# Component_Schematics.net
KiCad netlist of a schematic drawn in Altium Designer
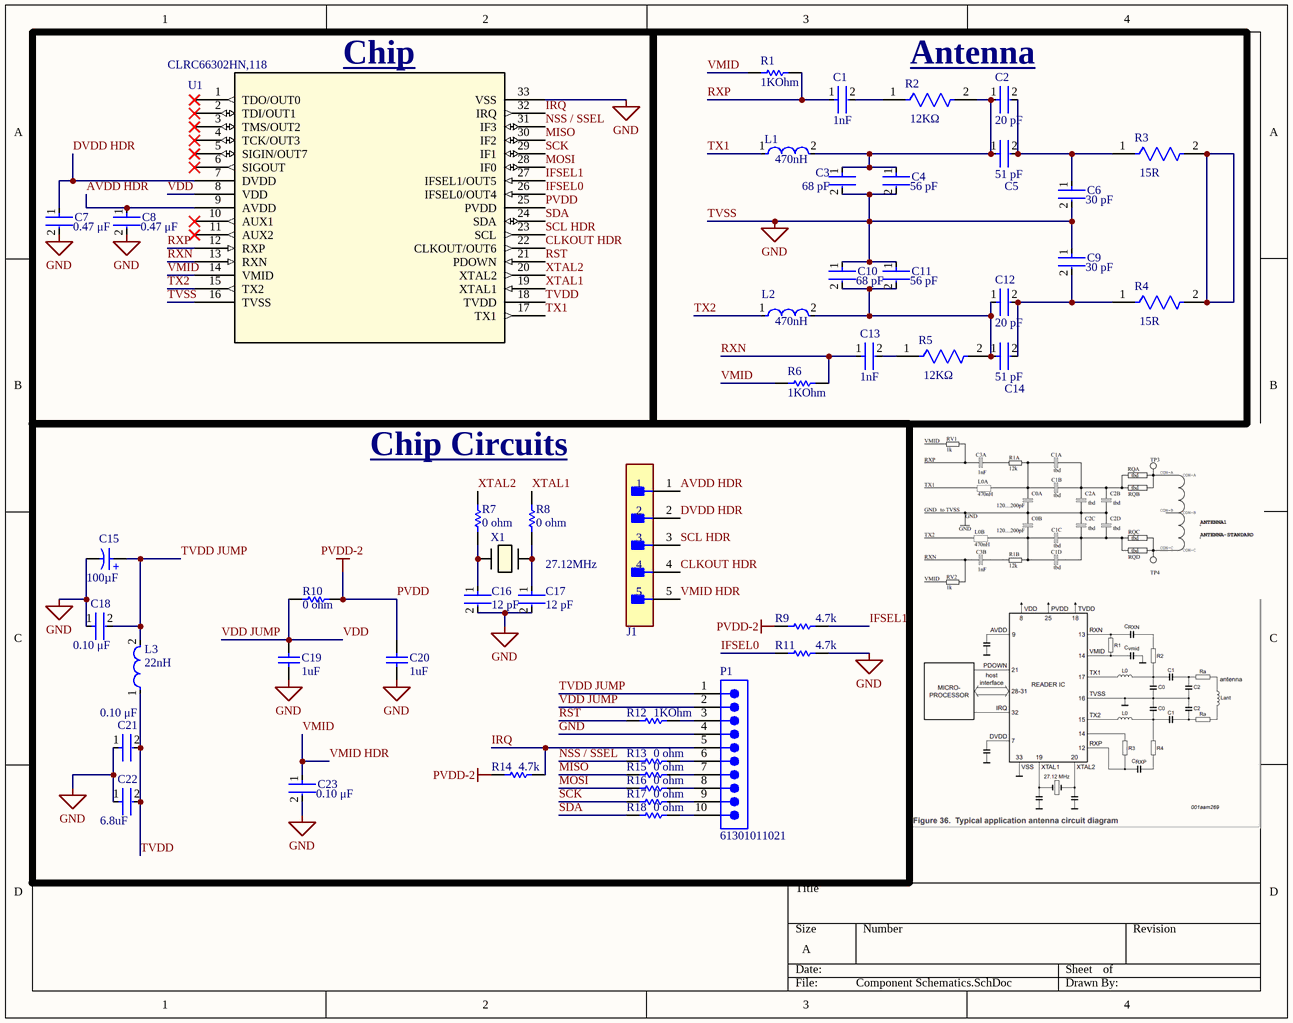
[diagram p0: Component Schematics.SchDoc]

(export (version "E")
  (design (tool "Eeschema 10.0.6"))
  (components
    (comp (ref "C1")
      (value "06035C102KAT2A")
      (footprint "FP-0603-L_1_6_0_15-W_0_81-IPC_A")
      (description "General Purpose Ceramic Capacitor, 0603, 1nF, 10%, X7R, 15%, 50V")
      (fields
        (field (name "CAPACITANCE") "1nF")
        (field (name "VOLTAGE") "50V")
        (field (name "TOLERANCE") "10%")
      )
      (libsource (lib "Altium Content Vault") (part "02cd4be3c70576c341d710602a673aa"))
    )
    (comp (ref "C2")
      (value "C0402C200J5GACTU")
      (footprint "FP-C0402-BB-MFG")
      (description "CAP CER 20PF 50V 5% NP0 0402")
      (fields
        (field (name "OCTOPART") "https://octopart.com/c0402c200j5gactu-kemet-9143900")
        (field (name "TOLERANCE") "0.05")
        (field (name "CAPACITANCE") "20 pF")
      )
      (libsource (lib "Altium Content Vault") (part "b4654b650e69147ec39a6b967a45e02"))
    )
    (comp (ref "C3")
      (value "C0402C680J5GACTU")
      (footprint "FP-C0402-BB-MFG")
      (description "CAP CER 68PF 50V 5% NP0 0402")
      (fields
        (field (name "MANUFACTURER") "Kemet")
        (field (name "CAPACITANCE") "68 pF")
        (field (name "TOLERANCE") "0.05")
      )
      (libsource (lib "Altium Content Vault") (part "b4654b650e69147ec39a6b967a45e02"))
    )
    (comp (ref "C4")
      (value "C0603C560J5GACTU")
      (footprint "FP-C0603C-CF-MFG")
      (description "CAP CER 56PF 50V C0G/NP0 0603")
      (fields
        (field (name "OCTOPART") "https://octopart.com/c0603c560j5gactu-kemet-107933")
        (field (name "CAPACITANCE") "56 pF")
        (field (name "MANUFACTURER") "KEMET")
      )
      (libsource (lib "Altium Content Vault") (part "b4654b650e69147ec39a6b967a45e02"))
    )
    (comp (ref "C5")
      (value "C0603C510J5GACTU")
      (footprint "FP-C0603C-CF-MFG")
      (description "CAP CER 51PF 50V 5% NP0 0603")
      (fields
        (field (name "TOLERANCE") "0.05")
        (field (name "OCTOPART") "https://octopart.com/c0603c510j5gactu-kemet-9143750")
        (field (name "CAPACITANCE") "51 pF")
      )
      (libsource (lib "Altium Content Vault") (part "b4654b650e69147ec39a6b967a45e02"))
    )
    (comp (ref "C6")
      (value "30 pF")
      (footprint "FP-C0603C-CF-MFG")
      (description "CAP CER 30PF 50V 5% NP0 0603")
      (fields
        (field (name "MANUFACTURER PART NUMBER") "C0603C300J5GACTU")
        (field (name "MANUFACTURER") "KEMET")
      )
      (libsource (lib "Altium Content Vault") (part "b4654b650e69147ec39a6b967a45e02"))
    )
    (comp (ref "C7")
      (value "C0805C474K5RACTU")
      (footprint "FP-C0805C-DN-MFG")
      (description "CAP CER 0.47UF 50V 10% X7R 0805")
      (fields
        (field (name "CAPACITANCE") "0.47 μF")
        (field (name "MANUFACTURER") "KEMET")
        (field (name "OCTOPART") "https://octopart.com/c0805c474k5ractu-kemet-144543")
      )
      (libsource (lib "Altium Content Vault") (part "b4654b650e69147ec39a6b967a45e02"))
    )
    (comp (ref "C8")
      (value "C0805C474K5RACTU")
      (footprint "FP-C0805C-DN-MFG")
      (description "CAP CER 0.47UF 50V 10% X7R 0805")
      (fields
        (field (name "CAPACITANCE") "0.47 μF")
        (field (name "MANUFACTURER") "KEMET")
        (field (name "OCTOPART") "https://octopart.com/c0805c474k5ractu-kemet-144543")
      )
      (libsource (lib "Altium Content Vault") (part "b4654b650e69147ec39a6b967a45e02"))
    )
    (comp (ref "C9")
      (value "30 pF")
      (footprint "FP-C0603C-CF-MFG")
      (description "CAP CER 30PF 50V 5% NP0 0603")
      (fields
        (field (name "MANUFACTURER PART NUMBER") "C0603C300J5GACTU")
        (field (name "MANUFACTURER") "KEMET")
      )
      (libsource (lib "Altium Content Vault") (part "b4654b650e69147ec39a6b967a45e02"))
    )
    (comp (ref "C10")
      (value "C0402C680J5GACTU")
      (footprint "FP-C0402-BB-MFG")
      (description "CAP CER 68PF 50V 5% NP0 0402")
      (fields
        (field (name "MANUFACTURER") "Kemet")
        (field (name "CAPACITANCE") "68 pF")
        (field (name "TOLERANCE") "0.05")
      )
      (libsource (lib "Altium Content Vault") (part "b4654b650e69147ec39a6b967a45e02"))
    )
    (comp (ref "C11")
      (value "C0603C560J5GACTU")
      (footprint "FP-C0603C-CF-MFG")
      (description "CAP CER 56PF 50V C0G/NP0 0603")
      (fields
        (field (name "OCTOPART") "https://octopart.com/c0603c560j5gactu-kemet-107933")
        (field (name "CAPACITANCE") "56 pF")
        (field (name "MANUFACTURER") "KEMET")
      )
      (libsource (lib "Altium Content Vault") (part "b4654b650e69147ec39a6b967a45e02"))
    )
    (comp (ref "C12")
      (value "C0402C200J5GACTU")
      (footprint "FP-C0402-BB-MFG")
      (description "CAP CER 20PF 50V 5% NP0 0402")
      (fields
        (field (name "OCTOPART") "https://octopart.com/c0402c200j5gactu-kemet-9143900")
        (field (name "TOLERANCE") "0.05")
        (field (name "CAPACITANCE") "20 pF")
      )
      (libsource (lib "Altium Content Vault") (part "b4654b650e69147ec39a6b967a45e02"))
    )
    (comp (ref "C13")
      (value "06035C102KAT2A")
      (footprint "FP-0603-L_1_6_0_15-W_0_81-IPC_A")
      (description "General Purpose Ceramic Capacitor, 0603, 1nF, 10%, X7R, 15%, 50V")
      (fields
        (field (name "CAPACITANCE") "1nF")
        (field (name "VOLTAGE") "50V")
        (field (name "TOLERANCE") "10%")
      )
      (libsource (lib "Altium Content Vault") (part "02cd4be3c70576c341d710602a673aa"))
    )
    (comp (ref "C14")
      (value "C0603C510J5GACTU")
      (footprint "FP-C0603C-CF-MFG")
      (description "CAP CER 51PF 50V 5% NP0 0603")
      (fields
        (field (name "TOLERANCE") "0.05")
        (field (name "OCTOPART") "https://octopart.com/c0603c510j5gactu-kemet-9143750")
        (field (name "CAPACITANCE") "51 pF")
      )
      (libsource (lib "Altium Content Vault") (part "b4654b650e69147ec39a6b967a45e02"))
    )
    (comp (ref "C15")
      (value "865060653010")
      (footprint "WCAP-ASLL_D8H10.5")
      (fields (field (name "CAPACITANCE") "100µF") (field (name "TOLERANCE") "20%"))
      (libsource (lib "Altium Content Vault") (part "Capacitor_Polarized"))
    )
    (comp (ref "C16")
      (value "12 pF")
      (footprint "FP-C0603C-CF-MFG")
      (description "Ceramic Capacitor 12Pf 50V, C0G, 5%, 0603, Full Reel")
      (fields (field (name "MANUFACTURER") "KEMET") (field (name "TOLERANCE") "0.05"))
      (libsource (lib "Altium Content Vault") (part "b4654b650e69147ec39a6b967a45e02"))
    )
    (comp (ref "C17")
      (value "12 pF")
      (footprint "FP-C0603C-CF-MFG")
      (description "Ceramic Capacitor 12Pf 50V, C0G, 5%, 0603, Full Reel")
      (fields (field (name "MANUFACTURER") "KEMET") (field (name "TOLERANCE") "0.05"))
      (libsource (lib "Altium Content Vault") (part "b4654b650e69147ec39a6b967a45e02"))
    )
    (comp (ref "C18")
      (value "C0402C104K8PACTU")
      (footprint "FP-C0402-BB-MFG")
      (description "CAP CER 0.1UF 10V X5R 0402")
      (fields
        (field (name "CAPACITANCE") "0.10 μF")
        (field (name "MANUFACTURER") "Kemet")
        (field (name "TOLERANCE") "0.1")
      )
      (libsource (lib "Altium Content Vault") (part "b4654b650e69147ec39a6b967a45e02"))
    )
    (comp (ref "C19")
      (value "C1206C105K5RACTU")
      (footprint "CAPC3216X110X50LL20T25")
      (description "Chip Capacitor, 1 uF, +/- 10%, 50 V, -55 to 125 degC, 1206 (3216 Metric), RoHS, Tape and Reel")
      (fields
        (field (name "CAPACITANCE") "1uF")
        (field (name "MANUFACTURER") "Kemet")
        (field (name "TOLERANCE") "10%")
      )
      (libsource (lib "Altium Content Vault") (part "CAP-NP-2"))
    )
    (comp (ref "C20")
      (value "C1206C105K5RACTU")
      (footprint "CAPC3216X110X50LL20T25")
      (description "Chip Capacitor, 1 uF, +/- 10%, 50 V, -55 to 125 degC, 1206 (3216 Metric), RoHS, Tape and Reel")
      (fields
        (field (name "CAPACITANCE") "1uF")
        (field (name "MANUFACTURER") "Kemet")
        (field (name "TOLERANCE") "10%")
      )
      (libsource (lib "Altium Content Vault") (part "CAP-NP-2"))
    )
    (comp (ref "C21")
      (value "C0402C104K8PACTU")
      (footprint "FP-C0402-BB-MFG")
      (description "CAP CER 0.1UF 10V X5R 0402")
      (fields
        (field (name "CAPACITANCE") "0.10 μF")
        (field (name "MANUFACTURER") "Kemet")
        (field (name "TOLERANCE") "0.1")
      )
      (libsource (lib "Altium Content Vault") (part "b4654b650e69147ec39a6b967a45e02"))
    )
    (comp (ref "C22")
      (value "C4532X7R1H685K250KB")
      (footprint "FP-C4532-250-0_4-IPC_C")
      (description "Multilayer Ceramic Capacitors 6.8uF ±10% 50V X7R SMD 1812")
      (fields
        (field (name "VOLTAGE") "50V")
        (field (name "CAPACITANCE") "6.8uF")
        (field (name "TOLERANCE") "10%")
      )
      (libsource (lib "Altium Content Vault") (part "02cd4be3c70576c341d710602a673aa"))
    )
    (comp (ref "C23")
      (value "C0402C104K8PACTU")
      (footprint "FP-C0402-BB-MFG")
      (description "CAP CER 0.1UF 10V X5R 0402")
      (fields
        (field (name "CAPACITANCE") "0.10 μF")
        (field (name "MANUFACTURER") "Kemet")
        (field (name "TOLERANCE") "0.1")
      )
      (libsource (lib "Altium Content Vault") (part "b4654b650e69147ec39a6b967a45e02"))
    )
    (comp (ref "J1")
      (value "22-28-4050")
      (footprint "FP-22-28-4050-MFG")
      (libsource (lib "Altium Content Vault") (part "bf93c07fd2649a848d0ec8585582aab"))
    )
    (comp (ref "L1")
      (value "IHLP2020CZERR47M01")
      (footprint "FP-IHLP-2020CZ-FP_1_905x2-MFG")
      (description "Fixed Inductors Commercial High Saturation Series 0.47uH 12.2A 7.04mΩ 20%")
      (fields (field (name "TOLERANCE") "20%") (field (name "INDUCTANCE") "470nH"))
      (libsource (lib "Altium Content Vault") (part "725321dda6339637d4d059423bc1c3c"))
    )
    (comp (ref "L2")
      (value "IHLP2020CZERR47M01")
      (footprint "FP-IHLP-2020CZ-FP_1_905x2-MFG")
      (description "Fixed Inductors Commercial High Saturation Series 0.47uH 12.2A 7.04mΩ 20%")
      (fields (field (name "TOLERANCE") "20%") (field (name "INDUCTANCE") "470nH"))
      (libsource (lib "Altium Content Vault") (part "725321dda6339637d4d059423bc1c3c"))
    )
    (comp (ref "L3")
      (value "LQW18AN22NG00D")
      (footprint "FP-LQW18AN_00-MFG")
      (description "Wire Wound RF Inductor 22nH ±2% 500mA 0.17Ω 0603 (1608)")
      (fields (field (name "TOLERANCE") "2%") (field (name "INDUCTANCE") "22nH"))
      (libsource (lib "Altium Content Vault") (part "725321dda6339637d4d059423bc1c3c"))
    )
    (comp (ref "P1")
      (value "61301011021")
      (footprint "61301011021")
      (libsource (lib "Altium Content Vault") (part "Header_Male_1R_10P"))
    )
    (comp (ref "R1")
      (value "RC0805FR-071KL")
      (footprint "RESC2013X60X35ML10T20")
      (description "Chip Resistor, 1 KOhm, +/- 1%, 125 mW, -55 to 155 degC, 0805 (2012 Metric), RoHS, Tape and Reel")
      (fields
        (field (name "RESISTANCE") "1KOhm")
        (field (name "TOLERANCE") "1%")
        (field (name "MANUFACTURER") "Yageo")
      )
      (libsource (lib "Altium Content Vault") (part "RES-2"))
    )
    (comp (ref "R2")
      (value "RT1206BRD0712KL")
      (footprint "FP-RT1206-MFG")
      (description "RES SMD 12K OHM 0.1% 1/4W 1206")
      (fields
        (field (name "MANUFACTURER") "Yageo")
        (field (name "OCTOPART") "https://octopart.com/rt1206brd0712kl-yageo-1232840")
        (field (name "RESISTANCE") "12KΩ")
      )
      (libsource (lib "Altium Content Vault") (part "1029c3af85768c4190bb7ad29bc67b5"))
    )
    (comp (ref "R3")
      (value "CRCW060315R0FKEA")
      (footprint "FP-CRCW0603-e3-MFG")
      (description "RES Thick Film, 15Ω, 1%, 0.1W, 100ppm/°C, 0603")
      (fields (field (name "TOLERANCE") "1%") (field (name "RESISTANCE") "15R"))
      (libsource (lib "Altium Content Vault") (part "1029c3af85768c4190bb7ad29bc67b5"))
    )
    (comp (ref "R4")
      (value "CRCW060315R0FKEA")
      (footprint "FP-CRCW0603-e3-MFG")
      (description "RES Thick Film, 15Ω, 1%, 0.1W, 100ppm/°C, 0603")
      (fields (field (name "TOLERANCE") "1%") (field (name "RESISTANCE") "15R"))
      (libsource (lib "Altium Content Vault") (part "1029c3af85768c4190bb7ad29bc67b5"))
    )
    (comp (ref "R5")
      (value "RT1206BRD0712KL")
      (footprint "FP-RT1206-MFG")
      (description "RES SMD 12K OHM 0.1% 1/4W 1206")
      (fields
        (field (name "MANUFACTURER") "Yageo")
        (field (name "OCTOPART") "https://octopart.com/rt1206brd0712kl-yageo-1232840")
        (field (name "RESISTANCE") "12KΩ")
      )
      (libsource (lib "Altium Content Vault") (part "1029c3af85768c4190bb7ad29bc67b5"))
    )
    (comp (ref "R6")
      (value "RC0805FR-071KL")
      (footprint "RESC2013X60X35ML10T20")
      (description "Chip Resistor, 1 KOhm, +/- 1%, 125 mW, -55 to 155 degC, 0805 (2012 Metric), RoHS, Tape and Reel")
      (fields
        (field (name "RESISTANCE") "1KOhm")
        (field (name "TOLERANCE") "1%")
        (field (name "MANUFACTURER") "Yageo")
      )
      (libsource (lib "Altium Content Vault") (part "RES-2"))
    )
    (comp (ref "R7")
      (value "RC0603JR-070RL")
      (footprint "RESC1608X55X25ML10T15")
      (description "Chip Resistor, 0 Ohm, +/- 5%, 0.1 W, -55 to 155 degC, 0603 (1608 Metric), RoHS, Tape and Reel")
      (fields
        (field (name "TOLERANCE") "5%")
        (field (name "RESISTANCE") "0 ohm")
        (field (name "MANUFACTURER") "Yageo")
      )
      (libsource (lib "Altium Content Vault") (part "RES-2"))
    )
    (comp (ref "R8")
      (value "RC0603JR-070RL")
      (footprint "RESC1608X55X25ML10T15")
      (description "Chip Resistor, 0 Ohm, +/- 5%, 0.1 W, -55 to 155 degC, 0603 (1608 Metric), RoHS, Tape and Reel")
      (fields
        (field (name "TOLERANCE") "5%")
        (field (name "RESISTANCE") "0 ohm")
        (field (name "MANUFACTURER") "Yageo")
      )
      (libsource (lib "Altium Content Vault") (part "RES-2"))
    )
    (comp (ref "R9")
      (value "RK73B1JTTD472J")
      (footprint "RESC1608X55X30ML20T10")
      (fields (field (name "MANUFACTURER") "KOA Speer") (field (name "RESISTANCE") "4.7k"))
      (libsource (lib "Altium Content Vault") (part "RES"))
    )
    (comp (ref "R10")
      (value "RC0603JR-070RL")
      (footprint "RESC1608X55X25ML10T15")
      (description "Chip Resistor, 0 Ohm, +/- 5%, 0.1 W, -55 to 155 degC, 0603 (1608 Metric), RoHS, Tape and Reel")
      (fields
        (field (name "TOLERANCE") "5%")
        (field (name "RESISTANCE") "0 ohm")
        (field (name "MANUFACTURER") "Yageo")
      )
      (libsource (lib "Altium Content Vault") (part "RES-2"))
    )
    (comp (ref "R11")
      (value "RK73B1JTTD472J")
      (footprint "RESC1608X55X30ML20T10")
      (fields (field (name "MANUFACTURER") "KOA Speer") (field (name "RESISTANCE") "4.7k"))
      (libsource (lib "Altium Content Vault") (part "RES"))
    )
    (comp (ref "R12")
      (value "RC1206FR-071KL")
      (footprint "RESC3116X65X40ML10T20")
      (description "Chip Resistor, 1 KOhm, +/- 1%, 0.25 W, -55 to 155 degC, 1206 (3216 Metric), RoHS, Tape and Reel")
      (fields
        (field (name "TOLERANCE") "1%")
        (field (name "MANUFACTURER") "Yageo")
        (field (name "RESISTANCE") "1KOhm")
      )
      (libsource (lib "Altium Content Vault") (part "RES-2"))
    )
    (comp (ref "R13")
      (value "RC0603JR-070RL")
      (footprint "RESC1608X55X25ML10T15")
      (description "Chip Resistor, 0 Ohm, +/- 5%, 0.1 W, -55 to 155 degC, 0603 (1608 Metric), RoHS, Tape and Reel")
      (fields
        (field (name "TOLERANCE") "5%")
        (field (name "RESISTANCE") "0 ohm")
        (field (name "MANUFACTURER") "Yageo")
      )
      (libsource (lib "Altium Content Vault") (part "RES-2"))
    )
    (comp (ref "R14")
      (value "RK73B1JTTD472J")
      (footprint "RESC1608X55X30ML20T10")
      (fields (field (name "MANUFACTURER") "KOA Speer") (field (name "RESISTANCE") "4.7k"))
      (libsource (lib "Altium Content Vault") (part "RES"))
    )
    (comp (ref "R15")
      (value "RC0603JR-070RL")
      (footprint "RESC1608X55X25ML10T15")
      (description "Chip Resistor, 0 Ohm, +/- 5%, 0.1 W, -55 to 155 degC, 0603 (1608 Metric), RoHS, Tape and Reel")
      (fields
        (field (name "TOLERANCE") "5%")
        (field (name "RESISTANCE") "0 ohm")
        (field (name "MANUFACTURER") "Yageo")
      )
      (libsource (lib "Altium Content Vault") (part "RES-2"))
    )
    (comp (ref "R16")
      (value "RC0603JR-070RL")
      (footprint "RESC1608X55X25ML10T15")
      (description "Chip Resistor, 0 Ohm, +/- 5%, 0.1 W, -55 to 155 degC, 0603 (1608 Metric), RoHS, Tape and Reel")
      (fields
        (field (name "TOLERANCE") "5%")
        (field (name "RESISTANCE") "0 ohm")
        (field (name "MANUFACTURER") "Yageo")
      )
      (libsource (lib "Altium Content Vault") (part "RES-2"))
    )
    (comp (ref "R17")
      (value "RC0603JR-070RL")
      (footprint "RESC1608X55X25ML10T15")
      (description "Chip Resistor, 0 Ohm, +/- 5%, 0.1 W, -55 to 155 degC, 0603 (1608 Metric), RoHS, Tape and Reel")
      (fields
        (field (name "TOLERANCE") "5%")
        (field (name "RESISTANCE") "0 ohm")
        (field (name "MANUFACTURER") "Yageo")
      )
      (libsource (lib "Altium Content Vault") (part "RES-2"))
    )
    (comp (ref "R18")
      (value "RC0603JR-070RL")
      (footprint "RESC1608X55X25ML10T15")
      (description "Chip Resistor, 0 Ohm, +/- 5%, 0.1 W, -55 to 155 degC, 0603 (1608 Metric), RoHS, Tape and Reel")
      (fields
        (field (name "TOLERANCE") "5%")
        (field (name "RESISTANCE") "0 ohm")
        (field (name "MANUFACTURER") "Yageo")
      )
      (libsource (lib "Altium Content Vault") (part "RES-2"))
    )
    (comp (ref "U1")
      (value "CLRC66302HN,118")
      (footprint "HVQFN32_SOT617-1_NXP")
      (description "Telecom Circuit, 1-Func, CMOS, PQCC32")
      (fields
        (field (name "MANUFACTURER") "NXP Semiconductors")
        (field (name "COPYRIGHT") "Copyright (C) 2023 Ultra Librarian. All rights reserved.")
      )
      (libsource (lib "*") (part "CLRC66302HN,118"))
    )
    (comp (ref "X1")
      (value "LFXTAL036075BULK")
      (footprint "XTAL_LFXTAL0360_IQD")
      (description "Parallel - Fundamental Quartz Crystal, 27.12MHz Nom")
      (fields
        (field (name "MANUFACTURER") "IQD")
        (field (name "CLOCK SPEED") "27.12MHz")
        (field (name "COPYRIGHT") "Copyright (C) 2023 Ultra Librarian. All rights reserved.")
      )
      (libsource (lib "LFXTAL036075BULK") (part "LFXTAL036075BULK"))
    )
  )
  (nets
    (net (code "1") (name "/AVDD HDR") (class "Default")
      (node (ref "C8") (pin "1") (pinfunction "1_1") (pintype "passive"))
      (node (ref "J1") (pin "1") (pinfunction "1_1") (pintype "passive"))
      (node (ref "U1") (pin "9") (pinfunction "AVDD_9") (pintype "power_in"))
    )
    (net (code "2") (name "/CLKOUT HDR") (class "Default")
      (node (ref "J1") (pin "4") (pinfunction "4_4") (pintype "passive"))
      (node (ref "U1") (pin "22") (pinfunction "CLKOUT/OUT6_22") (pintype "output"))
    )
    (net (code "3") (name "/DVDD HDR") (class "Default")
      (node (ref "C7") (pin "1") (pinfunction "1_1") (pintype "passive"))
      (node (ref "J1") (pin "2") (pinfunction "2_2") (pintype "passive"))
      (node (ref "U1") (pin "7") (pinfunction "DVDD_7") (pintype "power_in"))
    )
    (net (code "4") (name "/IFSEL0") (class "Default")
      (node (ref "R11") (pin "2") (pinfunction "2_2") (pintype "passive"))
      (node (ref "U1") (pin "26") (pinfunction "IFSEL0/OUT4_26") (pintype "input"))
    )
    (net (code "5") (name "/IFSEL1") (class "Default")
      (node (ref "R9") (pin "1") (pinfunction "1_1") (pintype "passive"))
      (node (ref "U1") (pin "27") (pinfunction "IFSEL1/OUT5_27") (pintype "input"))
    )
    (net (code "6") (name "/IRQ") (class "Default")
      (node (ref "P1") (pin "5") (pinfunction "5_5") (pintype "passive"))
      (node (ref "R14") (pin "2") (pinfunction "2_2") (pintype "passive"))
      (node (ref "U1") (pin "32") (pinfunction "IRQ_32") (pintype "output"))
    )
    (net (code "7") (name "/MISO") (class "Default")
      (node (ref "R15") (pin "1") (pinfunction "1_1") (pintype "passive"))
      (node (ref "U1") (pin "30") (pinfunction "IF2_30") (pintype "bidirectional"))
    )
    (net (code "8") (name "/MOSI") (class "Default")
      (node (ref "R16") (pin "1") (pinfunction "1_1") (pintype "passive"))
      (node (ref "U1") (pin "28") (pinfunction "IF0_28") (pintype "bidirectional"))
    )
    (net (code "9") (name "/NSS {slash} SSEL") (class "Default")
      (node (ref "R13") (pin "1") (pinfunction "1_1") (pintype "passive"))
      (node (ref "U1") (pin "31") (pinfunction "IF3_31") (pintype "bidirectional"))
    )
    (net (code "10") (name "/RST") (class "Default")
      (node (ref "R12") (pin "1") (pinfunction "1_1") (pintype "passive"))
      (node (ref "U1") (pin "21") (pinfunction "PDOWN_21") (pintype "input"))
    )
    (net (code "11") (name "/RXN") (class "Default")
      (node (ref "C13") (pin "1") (pinfunction "1_1") (pintype "passive"))
      (node (ref "R6") (pin "1") (pinfunction "1_1") (pintype "passive"))
      (node (ref "U1") (pin "13") (pinfunction "RXN_13") (pintype "input"))
    )
    (net (code "12") (name "/RXP") (class "Default")
      (node (ref "C1") (pin "1") (pinfunction "1_1") (pintype "passive"))
      (node (ref "R1") (pin "1") (pinfunction "1_1") (pintype "passive"))
      (node (ref "U1") (pin "12") (pinfunction "RXP_12") (pintype "input"))
    )
    (net (code "13") (name "/SCK") (class "Default")
      (node (ref "R17") (pin "1") (pinfunction "1_1") (pintype "passive"))
      (node (ref "U1") (pin "29") (pinfunction "IF1_29") (pintype "bidirectional"))
    )
    (net (code "14") (name "/SCL HDR") (class "Default")
      (node (ref "J1") (pin "3") (pinfunction "3_3") (pintype "passive"))
      (node (ref "U1") (pin "23") (pinfunction "SCL_23") (pintype "output"))
    )
    (net (code "15") (name "/SDA") (class "Default")
      (node (ref "R18") (pin "1") (pinfunction "1_1") (pintype "passive"))
      (node (ref "U1") (pin "24") (pinfunction "SDA_24") (pintype "bidirectional"))
    )
    (net (code "16") (name "/TVDD") (class "Default")
      (node (ref "C21") (pin "2") (pinfunction "2_2") (pintype "passive"))
      (node (ref "C22") (pin "2") (pinfunction "2_2") (pintype "passive"))
      (node (ref "L3") (pin "1") (pinfunction "1_1") (pintype "passive"))
      (node (ref "U1") (pin "18") (pinfunction "TVDD_18") (pintype "power_in"))
    )
    (net (code "17") (name "/TVDD JUMP") (class "Default")
      (node (ref "C15") (pin "1") (pinfunction "P_1") (pintype "passive"))
      (node (ref "C18") (pin "2") (pinfunction "2_2") (pintype "passive"))
      (node (ref "L3") (pin "2") (pinfunction "2_2") (pintype "passive"))
      (node (ref "P1") (pin "1") (pinfunction "1_1") (pintype "passive"))
    )
    (net (code "18") (name "/TX1") (class "Default")
      (node (ref "L1") (pin "1") (pinfunction "1_1") (pintype "passive"))
      (node (ref "U1") (pin "17") (pinfunction "TX1_17") (pintype "output"))
    )
    (net (code "19") (name "/TX2") (class "Default")
      (node (ref "L2") (pin "1") (pinfunction "1_1") (pintype "passive"))
      (node (ref "U1") (pin "15") (pinfunction "TX2_15") (pintype "output"))
    )
    (net (code "20") (name "/VDD") (class "Default")
      (node (ref "C19") (pin "2") (pinfunction "2_2") (pintype "passive"))
      (node (ref "P1") (pin "2") (pinfunction "2_2") (pintype "passive"))
      (node (ref "R10") (pin "1") (pinfunction "1_1") (pintype "passive"))
      (node (ref "U1") (pin "8") (pinfunction "VDD_8") (pintype "power_in"))
    )
    (net (code "21") (name "/VMID") (class "Default")
      (node (ref "C23") (pin "1") (pinfunction "1_1") (pintype "passive"))
      (node (ref "J1") (pin "5") (pinfunction "5_5") (pintype "passive"))
      (node (ref "R1") (pin "2") (pinfunction "2_2") (pintype "passive"))
      (node (ref "R6") (pin "2") (pinfunction "2_2") (pintype "passive"))
      (node (ref "U1") (pin "14") (pinfunction "VMID_14") (pintype "power_in"))
    )
    (net (code "22") (name "/XTAL1") (class "Default")
      (node (ref "R8") (pin "1") (pinfunction "1_1") (pintype "passive"))
      (node (ref "U1") (pin "19") (pinfunction "XTAL1_19") (pintype "input"))
    )
    (net (code "23") (name "/XTAL2") (class "Default")
      (node (ref "R7") (pin "1") (pinfunction "1_1") (pintype "passive"))
      (node (ref "U1") (pin "20") (pinfunction "XTAL2_20") (pintype "output"))
    )
    (net (code "24") (name "GND") (class "Default")
      (node (ref "C10") (pin "1") (pinfunction "1_1") (pintype "passive"))
      (node (ref "C11") (pin "1") (pinfunction "1_1") (pintype "passive"))
      (node (ref "C15") (pin "2") (pinfunction "N_2") (pintype "passive"))
      (node (ref "C16") (pin "2") (pinfunction "2_2") (pintype "passive"))
      (node (ref "C17") (pin "2") (pinfunction "2_2") (pintype "passive"))
      (node (ref "C18") (pin "1") (pinfunction "1_1") (pintype "passive"))
      (node (ref "C19") (pin "1") (pinfunction "1_1") (pintype "passive"))
      (node (ref "C20") (pin "1") (pinfunction "1_1") (pintype "passive"))
      (node (ref "C21") (pin "1") (pinfunction "1_1") (pintype "passive"))
      (node (ref "C22") (pin "1") (pinfunction "1_1") (pintype "passive"))
      (node (ref "C23") (pin "2") (pinfunction "2_2") (pintype "passive"))
      (node (ref "C3") (pin "2") (pinfunction "2_2") (pintype "passive"))
      (node (ref "C4") (pin "2") (pinfunction "2_2") (pintype "passive"))
      (node (ref "C6") (pin "2") (pinfunction "2_2") (pintype "passive"))
      (node (ref "C7") (pin "2") (pinfunction "2_2") (pintype "passive"))
      (node (ref "C8") (pin "2") (pinfunction "2_2") (pintype "passive"))
      (node (ref "C9") (pin "1") (pinfunction "1_1") (pintype "passive"))
      (node (ref "P1") (pin "4") (pinfunction "4_4") (pintype "passive"))
      (node (ref "R11") (pin "1") (pinfunction "1_1") (pintype "passive"))
      (node (ref "U1") (pin "16") (pinfunction "TVSS_16") (pintype "power_in"))
      (node (ref "U1") (pin "33") (pinfunction "VSS_33") (pintype "power_in"))
    )
    (net (code "25") (name "Net-(C1-Pad2)") (class "Default")
      (node (ref "C1") (pin "2") (pinfunction "2_2") (pintype "passive"))
      (node (ref "R2") (pin "1") (pinfunction "1_1") (pintype "passive"))
    )
    (net (code "26") (name "Net-(C2-Pad1)") (class "Default")
      (node (ref "C2") (pin "1") (pinfunction "1_1") (pintype "passive"))
      (node (ref "C3") (pin "1") (pinfunction "1_1") (pintype "passive"))
      (node (ref "C4") (pin "1") (pinfunction "1_1") (pintype "passive"))
      (node (ref "C5") (pin "1") (pinfunction "1_1") (pintype "passive"))
      (node (ref "L1") (pin "2") (pinfunction "2_2") (pintype "passive"))
      (node (ref "R2") (pin "2") (pinfunction "2_2") (pintype "passive"))
    )
    (net (code "27") (name "Net-(C2-Pad2)") (class "Default")
      (node (ref "C2") (pin "2") (pinfunction "2_2") (pintype "passive"))
      (node (ref "C5") (pin "2") (pinfunction "2_2") (pintype "passive"))
      (node (ref "C6") (pin "1") (pinfunction "1_1") (pintype "passive"))
      (node (ref "R3") (pin "1") (pinfunction "1_1") (pintype "passive"))
    )
    (net (code "28") (name "Net-(C10-Pad2)") (class "Default")
      (node (ref "C10") (pin "2") (pinfunction "2_2") (pintype "passive"))
      (node (ref "C11") (pin "2") (pinfunction "2_2") (pintype "passive"))
      (node (ref "C12") (pin "1") (pinfunction "1_1") (pintype "passive"))
      (node (ref "C14") (pin "1") (pinfunction "1_1") (pintype "passive"))
      (node (ref "L2") (pin "2") (pinfunction "2_2") (pintype "passive"))
      (node (ref "R5") (pin "2") (pinfunction "2_2") (pintype "passive"))
    )
    (net (code "29") (name "Net-(C12-Pad2)") (class "Default")
      (node (ref "C12") (pin "2") (pinfunction "2_2") (pintype "passive"))
      (node (ref "C14") (pin "2") (pinfunction "2_2") (pintype "passive"))
      (node (ref "C9") (pin "2") (pinfunction "2_2") (pintype "passive"))
      (node (ref "R4") (pin "1") (pinfunction "1_1") (pintype "passive"))
    )
    (net (code "30") (name "Net-(C13-Pad2)") (class "Default")
      (node (ref "C13") (pin "2") (pinfunction "2_2") (pintype "passive"))
      (node (ref "R5") (pin "1") (pinfunction "1_1") (pintype "passive"))
    )
    (net (code "31") (name "Net-(C16-Pad1)") (class "Default")
      (node (ref "C16") (pin "1") (pinfunction "1_1") (pintype "passive"))
      (node (ref "R7") (pin "2") (pinfunction "2_2") (pintype "passive"))
      (node (ref "X1") (pin "1") (pinfunction "1_1") (pintype "passive"))
    )
    (net (code "32") (name "Net-(C17-Pad1)") (class "Default")
      (node (ref "C17") (pin "1") (pinfunction "1_1") (pintype "passive"))
      (node (ref "R8") (pin "2") (pinfunction "2_2") (pintype "passive"))
      (node (ref "X1") (pin "2") (pinfunction "2_2") (pintype "passive"))
    )
    (net (code "33") (name "Net-(P1-Pad3)") (class "Default")
      (node (ref "P1") (pin "3") (pinfunction "3_3") (pintype "passive"))
      (node (ref "R12") (pin "2") (pinfunction "2_2") (pintype "passive"))
    )
    (net (code "34") (name "Net-(P1-Pad6)") (class "Default")
      (node (ref "P1") (pin "6") (pinfunction "6_6") (pintype "passive"))
      (node (ref "R13") (pin "2") (pinfunction "2_2") (pintype "passive"))
    )
    (net (code "35") (name "Net-(P1-Pad7)") (class "Default")
      (node (ref "P1") (pin "7") (pinfunction "7_7") (pintype "passive"))
      (node (ref "R15") (pin "2") (pinfunction "2_2") (pintype "passive"))
    )
    (net (code "36") (name "Net-(P1-Pad8)") (class "Default")
      (node (ref "P1") (pin "8") (pinfunction "8_8") (pintype "passive"))
      (node (ref "R16") (pin "2") (pinfunction "2_2") (pintype "passive"))
    )
    (net (code "37") (name "Net-(P1-Pad9)") (class "Default")
      (node (ref "P1") (pin "9") (pinfunction "9_9") (pintype "passive"))
      (node (ref "R17") (pin "2") (pinfunction "2_2") (pintype "passive"))
    )
    (net (code "38") (name "Net-(P1-Pad10)") (class "Default")
      (node (ref "P1") (pin "10") (pinfunction "10_10") (pintype "passive"))
      (node (ref "R18") (pin "2") (pinfunction "2_2") (pintype "passive"))
    )
    (net (code "39") (name "Net-(R3-Pad2)") (class "Default")
      (node (ref "R3") (pin "2") (pinfunction "2_2") (pintype "passive"))
      (node (ref "R4") (pin "2") (pinfunction "2_2") (pintype "passive"))
    )
    (net (code "40") (name "PVDD-2") (class "Default")
      (node (ref "C20") (pin "2") (pinfunction "2_2") (pintype "passive"))
      (node (ref "R10") (pin "2") (pinfunction "2_2") (pintype "passive"))
      (node (ref "R14") (pin "1") (pinfunction "1_1") (pintype "passive"))
      (node (ref "R9") (pin "2") (pinfunction "2_2") (pintype "passive"))
      (node (ref "U1") (pin "25") (pinfunction "PVDD_25") (pintype "power_in"))
    )
    (net (code "41") (name "unconnected-(U1-AUX1-Pad10)") (class "Default")
      (node (ref "U1") (pin "10") (pinfunction "AUX1_10") (pintype "output+no_connect"))
    )
    (net (code "42") (name "unconnected-(U1-AUX2-Pad11)") (class "Default")
      (node (ref "U1") (pin "11") (pinfunction "AUX2_11") (pintype "output+no_connect"))
    )
    (net (code "43") (name "unconnected-(U1-SIGIN{slash}OUT7-Pad5)") (class "Default")
      (node (ref "U1") (pin "5") (pinfunction "SIGIN/OUT7_5") (pintype "bidirectional+no_connect"))
    )
    (net (code "44") (name "unconnected-(U1-SIGOUT-Pad6)") (class "Default")
      (node (ref "U1") (pin "6") (pinfunction "SIGOUT_6") (pintype "output+no_connect"))
    )
    (net (code "45") (name "unconnected-(U1-TCK{slash}OUT3-Pad4)") (class "Default")
      (node (ref "U1") (pin "4") (pinfunction "TCK/OUT3_4") (pintype "bidirectional+no_connect"))
    )
    (net (code "46") (name "unconnected-(U1-TDI{slash}OUT1-Pad2)") (class "Default")
      (node (ref "U1") (pin "2") (pinfunction "TDI/OUT1_2") (pintype "bidirectional+no_connect"))
    )
    (net (code "47") (name "unconnected-(U1-TDO{slash}OUT0-Pad1)") (class "Default")
      (node (ref "U1") (pin "1") (pinfunction "TDO/OUT0_1") (pintype "output+no_connect"))
    )
    (net (code "48") (name "unconnected-(U1-TMS{slash}OUT2-Pad3)") (class "Default")
      (node (ref "U1") (pin "3") (pinfunction "TMS/OUT2_3") (pintype "bidirectional+no_connect"))
    )
  )
)
